# AUX_CON.net
KiCad netlist of a schematic drawn in Altium Designer
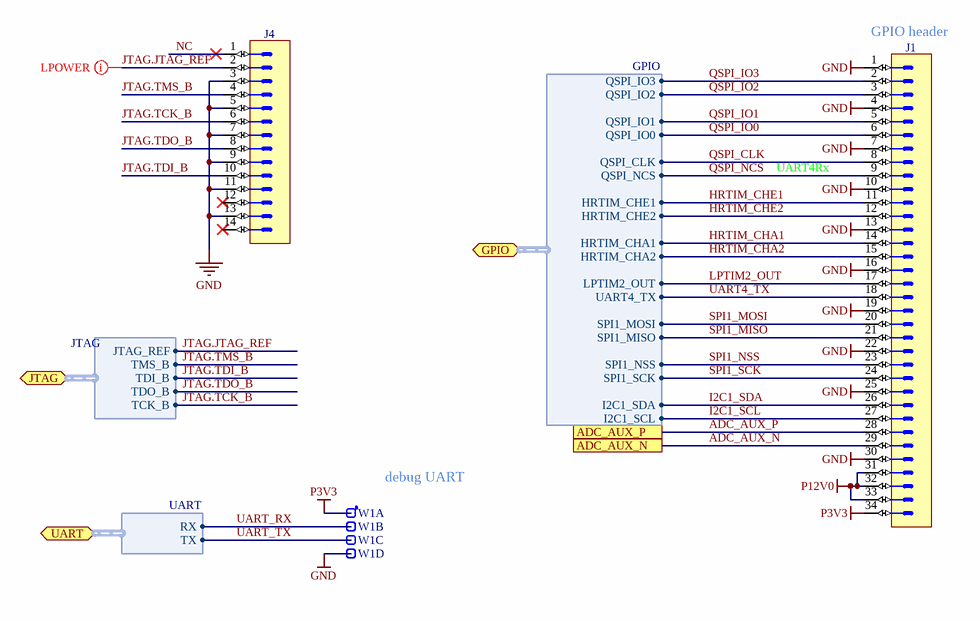
[diagram p0: AUX_CON.SchDoc]

(export (version "E")
  (design (tool "Eeschema 10.0.6"))
  (components
    (comp (ref "J1")
      (value "Header 34")
      (footprint "3M_N2534-6002RB")
      (description "Connector 34 Male")
      (fields
        (field (name "PART NUMBER") "3M_N2534-6002RB")
        (field (name "MANUFACTURER") "3M")
        (field (name "AUTHOR") "CERN DEM JLC")
      )
      (libsource (lib "Connectors") (part "Connector 34 Male"))
    )
    (comp (ref "J4")
      (value "Milli-Grid™")
      (footprint "MOLEX_87832-1420")
      (description "Connector 14 Male")
      (fields
        (field (name "PART NUMBER") "MOLEX_87832-1420")
        (field (name "MANUFACTURER") "MOLEX")
        (field (name "AUTHOR") "CERN DEM JLC")
      )
      (libsource (lib "Connectors") (part "Connector 14 Male"))
    )
    (comp (ref "W1")
      (value "Header 4")
      (footprint "SAMTEC_HTSW-104-23-L-S")
      (description "4 Mini Wire-Wrap Contact Strip Header")
      (fields
        (field (name "PART NUMBER") "SAMTEC_HTSW-104-23-L-S")
        (field (name "MANUFACTURER") "SAMTEC")
        (field (name "AUTHOR") "CERN DEM JLC")
      )
      (libsource (lib "Connectors") (part "Wire-Wrap Contact x4"))
    )
  )
  (nets
    (net (code "4") (name "/ADC_AUX_N") (class "Default")
      (node (ref "J1") (pin "29") (pinfunction "29_29") (pintype "bidirectional"))
    )
    (net (code "5") (name "/ADC_AUX_P") (class "Default")
      (node (ref "J1") (pin "28") (pinfunction "28_28") (pintype "bidirectional"))
    )
    (net (code "6") (name "/HRTIM_CHA1") (class "Default")
      (node (ref "J1") (pin "14") (pinfunction "14_14") (pintype "bidirectional"))
    )
    (net (code "7") (name "/HRTIM_CHA2") (class "Default")
      (node (ref "J1") (pin "15") (pinfunction "15_15") (pintype "bidirectional"))
    )
    (net (code "8") (name "/HRTIM_CHE1") (class "Default")
      (node (ref "J1") (pin "11") (pinfunction "11_11") (pintype "bidirectional"))
    )
    (net (code "9") (name "/HRTIM_CHE2") (class "Default")
      (node (ref "J1") (pin "12") (pinfunction "12_12") (pintype "bidirectional"))
    )
    (net (code "10") (name "/I2C1_SCL") (class "Default")
      (node (ref "J1") (pin "27") (pinfunction "27_27") (pintype "bidirectional"))
    )
    (net (code "11") (name "/I2C1_SDA") (class "Default")
      (node (ref "J1") (pin "26") (pinfunction "26_26") (pintype "bidirectional"))
    )
    (net (code "12") (name "/JTAG.JTAG_REF") (class "Default")
      (node (ref "J4") (pin "2") (pinfunction "2_2") (pintype "bidirectional"))
    )
    (net (code "13") (name "/JTAG.TCK_B") (class "Default")
      (node (ref "J4") (pin "6") (pinfunction "6_6") (pintype "bidirectional"))
    )
    (net (code "14") (name "/JTAG.TDI_B") (class "Default")
      (node (ref "J4") (pin "10") (pinfunction "10_10") (pintype "bidirectional"))
    )
    (net (code "15") (name "/JTAG.TDO_B") (class "Default")
      (node (ref "J4") (pin "8") (pinfunction "8_8") (pintype "bidirectional"))
    )
    (net (code "16") (name "/JTAG.TMS_B") (class "Default")
      (node (ref "J4") (pin "4") (pinfunction "4_4") (pintype "bidirectional"))
    )
    (net (code "17") (name "/LPTIM2_OUT") (class "Default")
      (node (ref "J1") (pin "17") (pinfunction "17_17") (pintype "bidirectional"))
    )
    (net (code "18") (name "/NC") (class "Default")
      (node (ref "J4") (pin "1") (pinfunction "1_1") (pintype "bidirectional"))
    )
    (net (code "19") (name "/QSPI_CLK") (class "Default")
      (node (ref "J1") (pin "8") (pinfunction "8_8") (pintype "bidirectional"))
    )
    (net (code "20") (name "/QSPI_IO0") (class "Default")
      (node (ref "J1") (pin "6") (pinfunction "6_6") (pintype "bidirectional"))
    )
    (net (code "21") (name "/QSPI_IO1") (class "Default")
      (node (ref "J1") (pin "5") (pinfunction "5_5") (pintype "bidirectional"))
    )
    (net (code "22") (name "/QSPI_IO2") (class "Default")
      (node (ref "J1") (pin "3") (pinfunction "3_3") (pintype "bidirectional"))
    )
    (net (code "23") (name "/QSPI_IO3") (class "Default")
      (node (ref "J1") (pin "2") (pinfunction "2_2") (pintype "bidirectional"))
    )
    (net (code "24") (name "/QSPI_NCS") (class "Default")
      (node (ref "J1") (pin "9") (pinfunction "9_9") (pintype "bidirectional"))
    )
    (net (code "25") (name "/SPI1_MISO") (class "Default")
      (node (ref "J1") (pin "21") (pinfunction "21_21") (pintype "bidirectional"))
    )
    (net (code "26") (name "/SPI1_MOSI") (class "Default")
      (node (ref "J1") (pin "20") (pinfunction "20_20") (pintype "bidirectional"))
    )
    (net (code "27") (name "/SPI1_NSS") (class "Default")
      (node (ref "J1") (pin "23") (pinfunction "23_23") (pintype "bidirectional"))
    )
    (net (code "28") (name "/SPI1_SCK") (class "Default")
      (node (ref "J1") (pin "24") (pinfunction "24_24") (pintype "bidirectional"))
    )
    (net (code "29") (name "/UART4_TX") (class "Default")
      (node (ref "J1") (pin "18") (pinfunction "18_18") (pintype "bidirectional"))
    )
    (net (code "30") (name "/UART_RX") (class "Default")
      (node (ref "W1") (pin "2") (pinfunction "2_2") (pintype "bidirectional"))
    )
    (net (code "31") (name "/UART_TX") (class "Default")
      (node (ref "W1") (pin "3") (pinfunction "3_3") (pintype "bidirectional"))
    )
    (net (code "35") (name "GND") (class "Default")
      (node (ref "J1") (pin "1") (pinfunction "1_1") (pintype "bidirectional"))
      (node (ref "J1") (pin "10") (pinfunction "10_10") (pintype "bidirectional"))
      (node (ref "J1") (pin "13") (pinfunction "13_13") (pintype "bidirectional"))
      (node (ref "J1") (pin "16") (pinfunction "16_16") (pintype "bidirectional"))
      (node (ref "J1") (pin "19") (pinfunction "19_19") (pintype "bidirectional"))
      (node (ref "J1") (pin "22") (pinfunction "22_22") (pintype "bidirectional"))
      (node (ref "J1") (pin "25") (pinfunction "25_25") (pintype "bidirectional"))
      (node (ref "J1") (pin "30") (pinfunction "30_30") (pintype "bidirectional"))
      (node (ref "J1") (pin "4") (pinfunction "4_4") (pintype "bidirectional"))
      (node (ref "J1") (pin "7") (pinfunction "7_7") (pintype "bidirectional"))
      (node (ref "J4") (pin "11") (pinfunction "11_11") (pintype "bidirectional"))
      (node (ref "J4") (pin "13") (pinfunction "13_13") (pintype "bidirectional"))
      (node (ref "J4") (pin "3") (pinfunction "3_3") (pintype "bidirectional"))
      (node (ref "J4") (pin "5") (pinfunction "5_5") (pintype "bidirectional"))
      (node (ref "J4") (pin "7") (pinfunction "7_7") (pintype "bidirectional"))
      (node (ref "J4") (pin "9") (pinfunction "9_9") (pintype "bidirectional"))
      (node (ref "W1") (pin "4") (pinfunction "4_4") (pintype "bidirectional"))
    )
    (net (code "36") (name "P3V3") (class "Default")
      (node (ref "J1") (pin "34") (pinfunction "34_34") (pintype "bidirectional"))
      (node (ref "W1") (pin "1") (pinfunction "1_1") (pintype "bidirectional"))
    )
    (net (code "37") (name "P12V0") (class "Default")
      (node (ref "J1") (pin "31") (pinfunction "31_31") (pintype "bidirectional"))
      (node (ref "J1") (pin "32") (pinfunction "32_32") (pintype "bidirectional"))
      (node (ref "J1") (pin "33") (pinfunction "33_33") (pintype "bidirectional"))
    )
    (net (code "38") (name "unconnected-(J4-Pad12)") (class "Default")
      (node (ref "J4") (pin "12") (pinfunction "12_12") (pintype "bidirectional+no_connect"))
    )
    (net (code "39") (name "unconnected-(J4-Pad14)") (class "Default")
      (node (ref "J4") (pin "14") (pinfunction "14_14") (pintype "bidirectional+no_connect"))
    )
  )
)
